# LED.net
KiCad netlist of a schematic drawn in Altium Designer
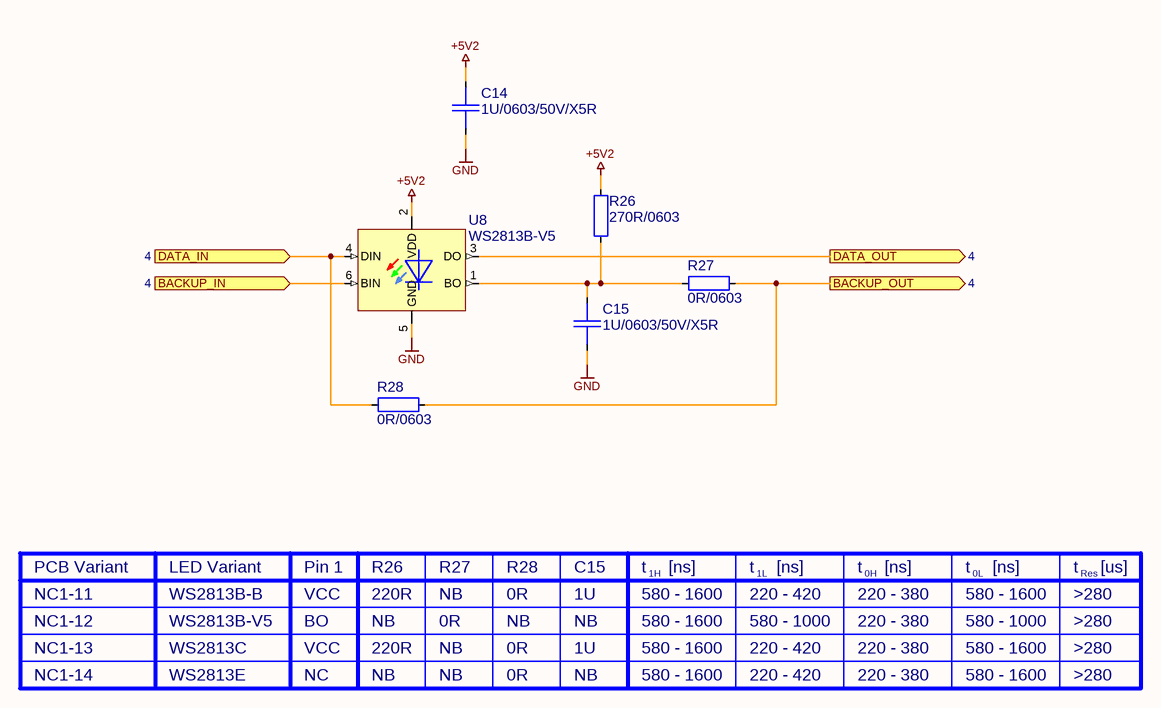
[diagram p0: LED.SchDoc]

(export (version "E")
  (design (tool "Eeschema 10.0.6"))
  (components
    (comp (ref "C14")
      (value "1U/0603/50V/X5R")
      (footprint "CAP0603_X7R")
      (description "CAP SM 0603 1.0uF 50V X5R")
      (fields (field (name "MANUFACTURER") "GENERIC"))
      (libsource (lib "daniw_altium_lib") (part "C"))
    )
    (comp (ref "C15")
      (value "1U/0603/50V/X5R")
      (footprint "CAP0603_X7R")
      (description "CAP SM 0603 1.0uF 50V X5R")
      (fields (field (name "MANUFACTURER") "GENERIC"))
      (libsource (lib "daniw_altium_lib") (part "C"))
    )
    (comp (ref "R26")
      (value "270R/0603")
      (footprint "R0603-0.40-WW")
      (description "RES SM 0603 270R")
      (fields (field (name "MANUFACTURER") "GENERIC"))
      (libsource (lib "daniw_altium_lib") (part "R"))
    )
    (comp (ref "R27")
      (value "0R/0603")
      (footprint "R0603-0.40-WW")
      (description "RES SM 0603 0R")
      (fields (field (name "MANUFACTURER") "GENERIC"))
      (libsource (lib "daniw_altium_lib") (part "R"))
    )
    (comp (ref "R28")
      (value "0R/0603")
      (footprint "R0603-0.40-WW")
      (description "RES SM 0603 0R")
      (fields (field (name "MANUFACTURER") "GENERIC"))
      (libsource (lib "daniw_altium_lib") (part "R"))
    )
    (comp (ref "U8")
      (value "WS2813B-V5")
      (footprint "LEDM5050X165-6-SE")
      (description "Intelligent control LED integrated light source with backup Pin")
      (fields (field (name "MANUFACTURER") "WorldSemi"))
      (libsource (lib "daniw_altium_lib") (part "WS2813_BO"))
    )
  )
  (nets
    (net (code "1") (name "+5V2") (class "Default")
      (node (ref "C14") (pin "1") (pinfunction "1_1") (pintype "passive"))
      (node (ref "R26") (pin "1") (pinfunction "1_1") (pintype "passive"))
      (node (ref "U8") (pin "2") (pinfunction "VDD_2") (pintype "passive"))
    )
    (net (code "2") (name "/BACKUP_IN") (class "Default")
      (node (ref "U8") (pin "6") (pinfunction "BIN_6") (pintype "input"))
    )
    (net (code "3") (name "/BACKUP_OUT") (class "Default")
      (node (ref "R27") (pin "2") (pinfunction "2_2") (pintype "passive"))
      (node (ref "R28") (pin "2") (pinfunction "2_2") (pintype "passive"))
    )
    (net (code "4") (name "/DATA_IN") (class "Default")
      (node (ref "R28") (pin "1") (pinfunction "1_1") (pintype "passive"))
      (node (ref "U8") (pin "4") (pinfunction "DIN_4") (pintype "input"))
    )
    (net (code "5") (name "/DATA_OUT") (class "Default")
      (node (ref "U8") (pin "3") (pinfunction "DO_3") (pintype "output"))
    )
    (net (code "6") (name "GND") (class "Default")
      (node (ref "C14") (pin "2") (pinfunction "2_2") (pintype "passive"))
      (node (ref "C15") (pin "2") (pinfunction "2_2") (pintype "passive"))
      (node (ref "U8") (pin "5") (pinfunction "GND_5") (pintype "passive"))
    )
    (net (code "7") (name "Net-(U8-BO)") (class "Default")
      (node (ref "C15") (pin "1") (pinfunction "1_1") (pintype "passive"))
      (node (ref "R26") (pin "2") (pinfunction "2_2") (pintype "passive"))
      (node (ref "R27") (pin "1") (pinfunction "1_1") (pintype "passive"))
      (node (ref "U8") (pin "1") (pinfunction "BO_1") (pintype "output"))
    )
  )
)
